# design.net
KiCad netlist of a schematic drawn in EasyEDA Pro
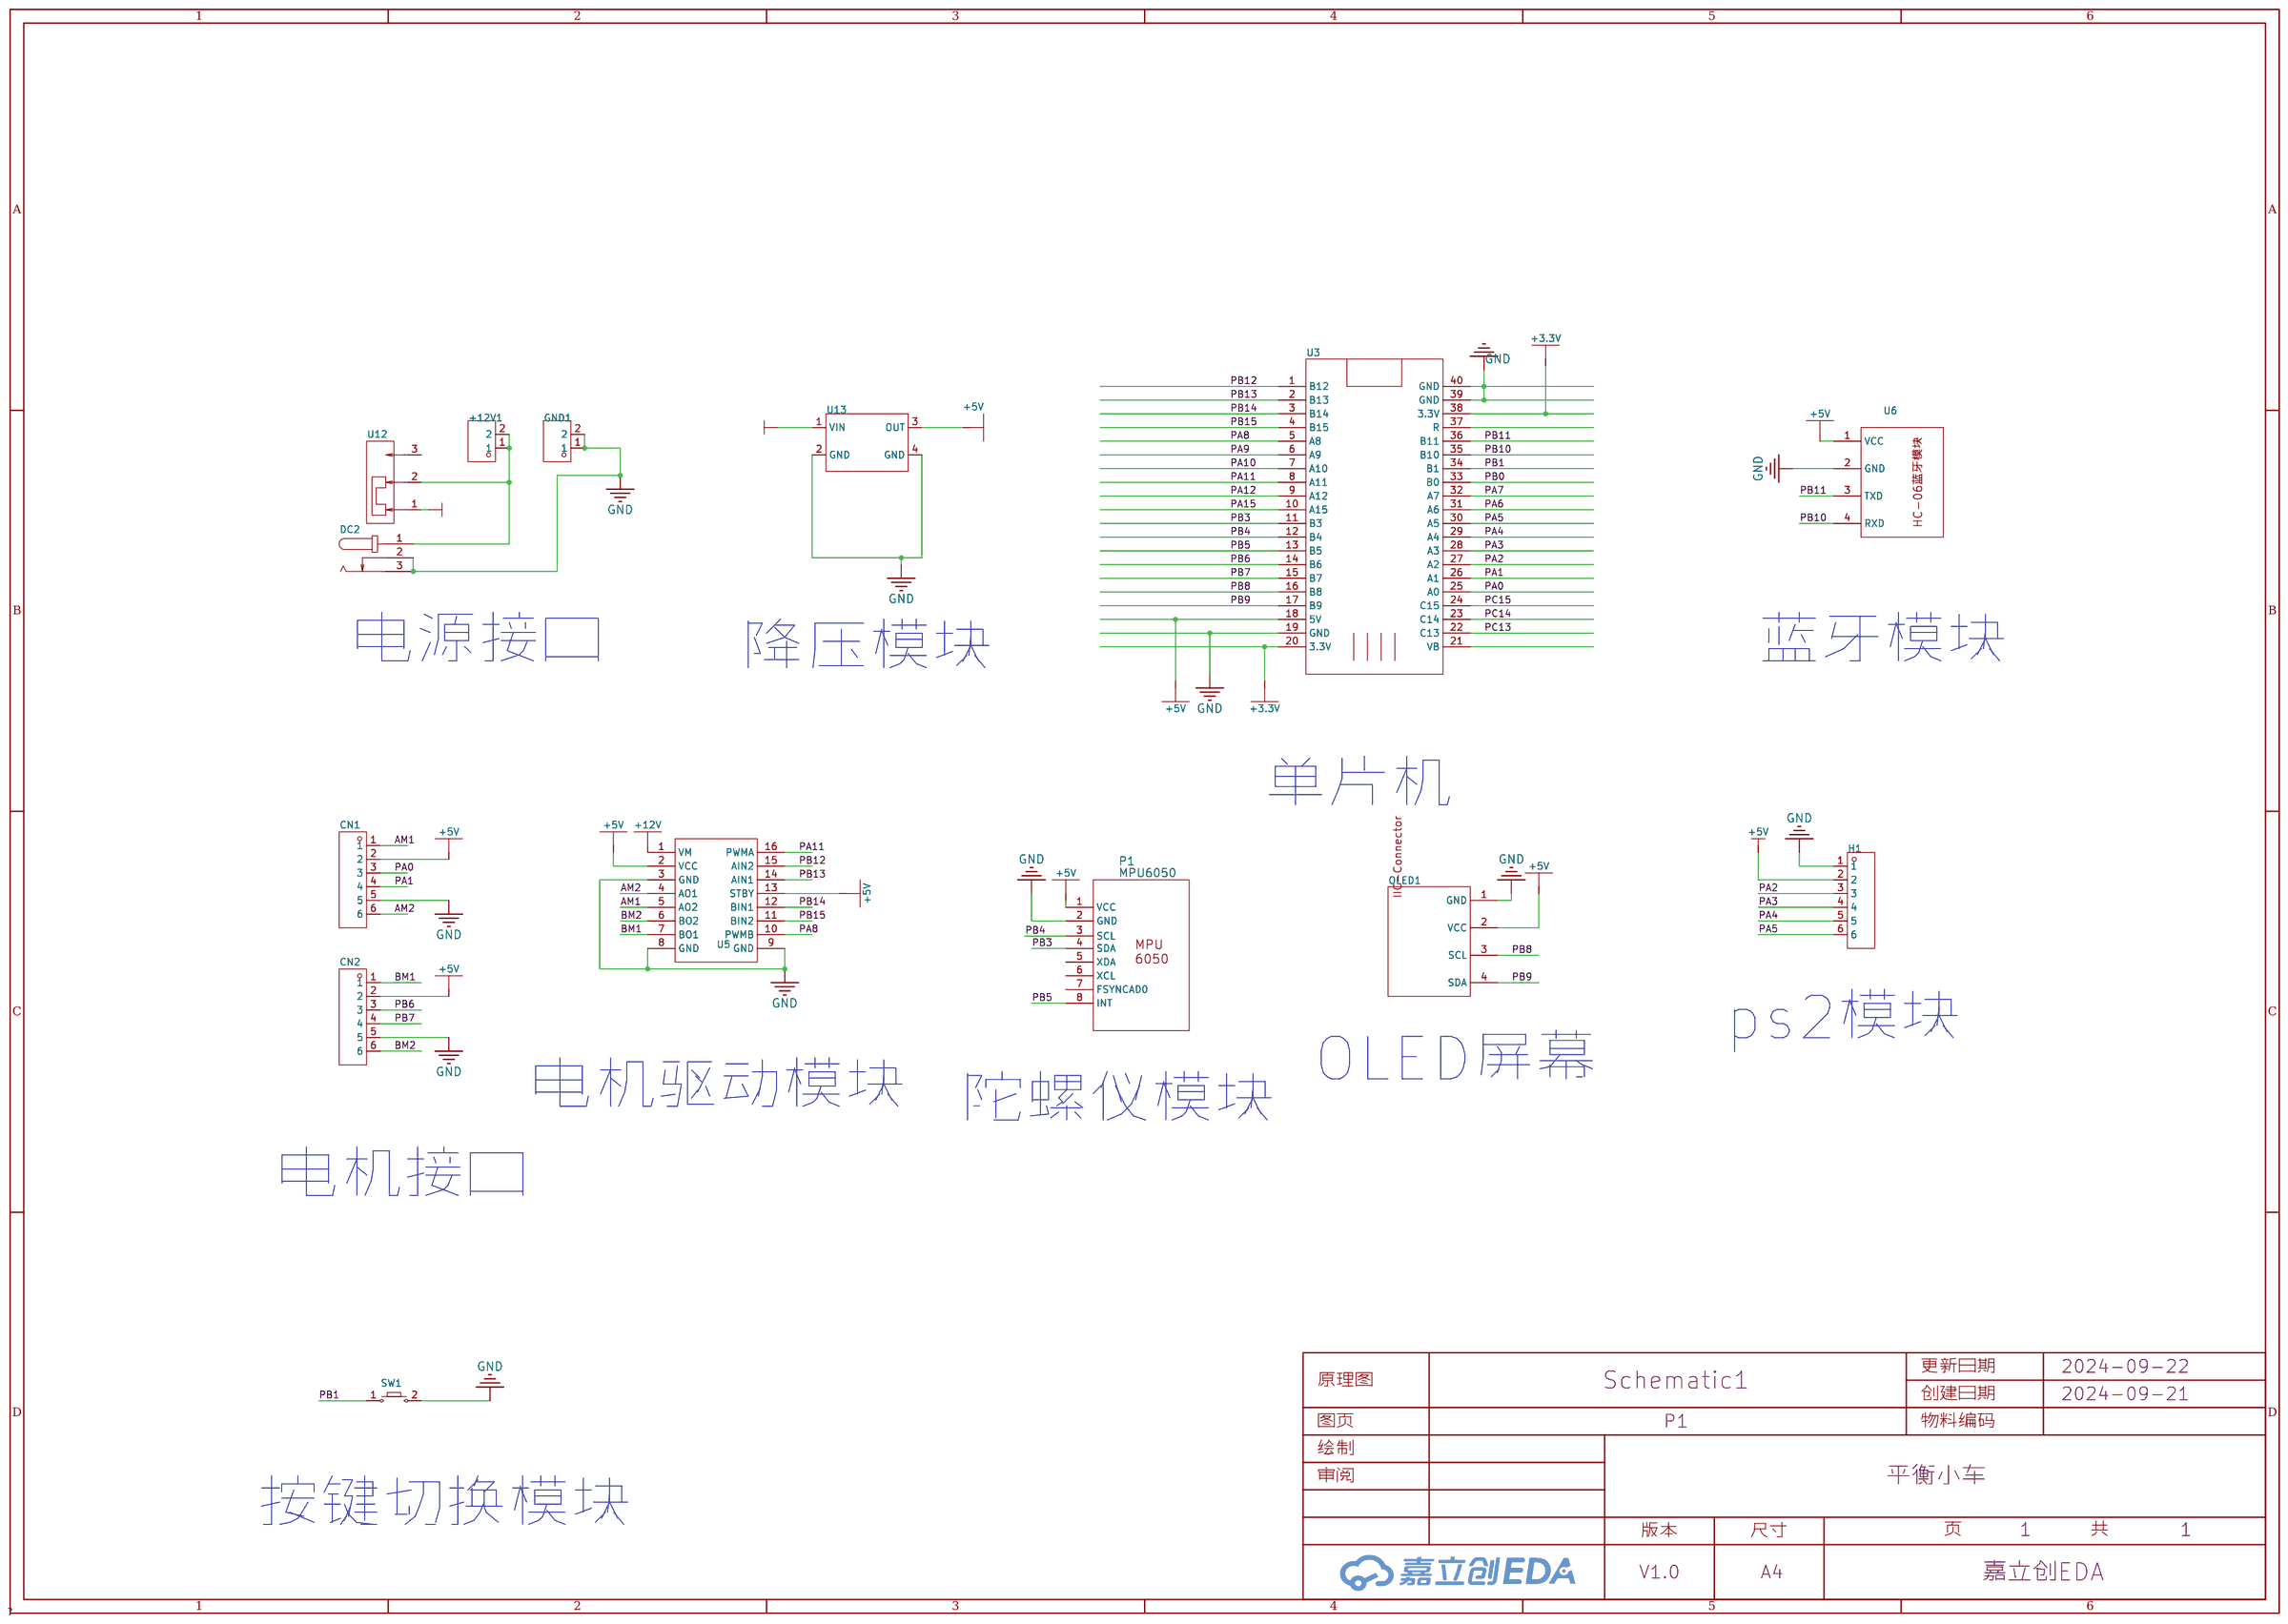
[diagram p0: schematic sheet]

(export (version "E")
  (design (tool "Eeschema 10.0.6"))
  (components
    (comp (ref "+12V1")
      (value "~")
      (description "2.54 1*2P 直排针 0.8u镀金 PBT RoHS,针长3*6mm")
      (fields
        (field (name "Manufacturer Part") "Z-211-0211-0021-001")
        (field (name "Manufacturer") "Nextron(台湾正凌)")
      )
      (libsource (lib "easyedapro") (part "Z-211-0211-0021-001"))
    )
    (comp (ref "CN1")
      (value "PH2.0-6P")
      (fields (field (name "Manufacturer Part") "PH2.0-4P") (field (name "Manufacturer") "CAX(创都)"))
      (libsource (lib "easyedapro") (part "PH2.0-6P"))
    )
    (comp (ref "CN2")
      (value "PH2.0-6P")
      (fields (field (name "Manufacturer Part") "PH2.0-4P") (field (name "Manufacturer") "CAX(创都)"))
      (libsource (lib "easyedapro") (part "ph2.0-6p"))
    )
    (comp (ref "DC2")
      (value "~")
      (description "连接器类型:DC电源插座;安装方式:弯插;触点内径:-;触点外径:6.4mm;额定电流:1A;额定电压:30V;工作温度范围:-25~+70;")
      (fields
        (field (name "Manufacturer Part") "KH-DC-005-2.5")
        (field (name "Manufacturer") "kinghelm(金航标)")
      )
      (libsource (lib "easyedapro") (part "KH-DC-005-2.5"))
    )
    (comp (ref "GND1")
      (value "~")
      (description "2.54 1*2P 直排针 0.8u镀金 PBT RoHS,针长3*6mm")
      (fields
        (field (name "Manufacturer Part") "Z-211-0211-0021-001")
        (field (name "Manufacturer") "Nextron(台湾正凌)")
      )
      (libsource (lib "easyedapro") (part "Z-211-0211-0021-001"))
    )
    (comp (ref "H1")
      (value "PZ254V-11-06P")
      (footprint "easyedapro:HDR-TH_6P-P2.54-V-M")
      (fields (field (name "Manufacturer") "XFCN(兴飞)"))
      (libsource (lib "easyedapro") (part "PZ254V-11-06P"))
    )
    (comp (ref "OLED1")
      (value "~")
      (fields (field (name "Manufacturer Part") "0.96OLED_4P_MODULE_JX"))
      (libsource (lib "easyedapro") (part "0.96OLED_4P_MODULE_JX"))
    )
    (comp (ref "P1") (value "MPU6050") (libsource (lib "easyedapro") (part "MPU6050")))
    (comp (ref "SW1")
      (value "~")
      (footprint "easyedapro:Key_SMD_3x4x2")
      (libsource (lib "easyedapro") (part "轻触按键x2"))
    )
    (comp (ref "U3") (value "~") (libsource (lib "easyedapro") (part "STM32F103C8T6核心板")))
    (comp (ref "U5") (value "~") (libsource (lib "easyedapro") (part "TB6612FNG模块")))
    (comp (ref "U6") (value "蓝牙模块HC-06") (libsource (lib "easyedapro") (part "蓝牙模块HC-06")))
    (comp (ref "U12")
      (value "SS-12D10-G5")
      (footprint "easyedapro:SW-TH_SS-12D10-G050")
      (description "电路结构:单刀双掷;安装方式:直插;开关颜色:黑色;滑钮形状:矩形柱状;引脚样式:PC引脚;开关长度:12.7mm;开关宽度:6.7mm;开关高度:11.3mm;")
      (fields (field (name "Manufacturer") "DEALON(德艺隆)"))
      (libsource (lib "easyedapro") (part "SS-12D10-G5"))
    )
    (comp (ref "U13")
      (value "~")
      (footprint "easyedapro:MP1584模块")
      (libsource (lib "easyedapro") (part "MP1584模块"))
    )
  )
  (nets
    (net (code "1") (name "+3.3V") (class "Default")
      (node (ref "U3") (pin "20") (pinfunction "3.3V_20") (pintype "unspecified"))
      (node (ref "U3") (pin "38") (pinfunction "3.3V_38") (pintype "unspecified"))
    )
    (net (code "2") (name "+5V") (class "Default")
      (node (ref "CN1") (pin "2") (pinfunction "2_2") (pintype "input"))
      (node (ref "CN2") (pin "2") (pinfunction "2_2") (pintype "input"))
      (node (ref "H1") (pin "2") (pinfunction "2_2") (pintype "unspecified"))
      (node (ref "OLED1") (pin "2") (pinfunction "VCC_2") (pintype "input"))
      (node (ref "P1") (pin "1") (pinfunction "VCC_1") (pintype "input"))
      (node (ref "U13") (pin "3") (pinfunction "OUT_3") (pintype "unspecified"))
      (node (ref "U3") (pin "18") (pinfunction "5V_18") (pintype "unspecified"))
      (node (ref "U5") (pin "13") (pinfunction "STBY_13") (pintype "input"))
      (node (ref "U5") (pin "2") (pinfunction "VCC_2") (pintype "input"))
      (node (ref "U6") (pin "1") (pinfunction "VCC_1") (pintype "unspecified"))
    )
    (net (code "3") (name "+12V") (class "Default")
      (node (ref "U12") (pin "1") (pinfunction "1_1") (pintype "input"))
      (node (ref "U13") (pin "1") (pinfunction "VIN_1") (pintype "unspecified"))
      (node (ref "U5") (pin "1") (pinfunction "VM_1") (pintype "input"))
    )
    (net (code "4") (name "/AM1") (class "Default")
      (node (ref "CN1") (pin "1") (pinfunction "1_1") (pintype "input"))
      (node (ref "U5") (pin "5") (pinfunction "AO2_5") (pintype "input"))
    )
    (net (code "5") (name "/AM2") (class "Default")
      (node (ref "CN1") (pin "6") (pinfunction "6_6") (pintype "input"))
      (node (ref "U5") (pin "4") (pinfunction "AO1_4") (pintype "input"))
    )
    (net (code "6") (name "/BM1") (class "Default")
      (node (ref "CN2") (pin "1") (pinfunction "1_1") (pintype "input"))
      (node (ref "U5") (pin "7") (pinfunction "BO1_7") (pintype "input"))
    )
    (net (code "7") (name "/BM2") (class "Default")
      (node (ref "CN2") (pin "6") (pinfunction "6_6") (pintype "input"))
      (node (ref "U5") (pin "6") (pinfunction "BO2_6") (pintype "input"))
    )
    (net (code "8") (name "/PA0") (class "Default")
      (node (ref "CN1") (pin "3") (pinfunction "3_3") (pintype "input"))
      (node (ref "U3") (pin "25") (pinfunction "A0_25") (pintype "unspecified"))
    )
    (net (code "9") (name "/PA1") (class "Default")
      (node (ref "CN1") (pin "4") (pinfunction "4_4") (pintype "input"))
      (node (ref "U3") (pin "26") (pinfunction "A1_26") (pintype "unspecified"))
    )
    (net (code "10") (name "/PA2") (class "Default")
      (node (ref "H1") (pin "3") (pinfunction "3_3") (pintype "unspecified"))
      (node (ref "U3") (pin "27") (pinfunction "A2_27") (pintype "unspecified"))
    )
    (net (code "11") (name "/PA3") (class "Default")
      (node (ref "H1") (pin "4") (pinfunction "4_4") (pintype "unspecified"))
      (node (ref "U3") (pin "28") (pinfunction "A3_28") (pintype "unspecified"))
    )
    (net (code "12") (name "/PA4") (class "Default")
      (node (ref "H1") (pin "5") (pinfunction "5_5") (pintype "unspecified"))
      (node (ref "U3") (pin "29") (pinfunction "A4_29") (pintype "unspecified"))
    )
    (net (code "13") (name "/PA5") (class "Default")
      (node (ref "H1") (pin "6") (pinfunction "6_6") (pintype "unspecified"))
      (node (ref "U3") (pin "30") (pinfunction "A5_30") (pintype "unspecified"))
    )
    (net (code "14") (name "/PA6") (class "Default")
      (node (ref "U3") (pin "31") (pinfunction "A6_31") (pintype "unspecified"))
    )
    (net (code "15") (name "/PA7") (class "Default")
      (node (ref "U3") (pin "32") (pinfunction "A7_32") (pintype "unspecified"))
    )
    (net (code "16") (name "/PA8") (class "Default")
      (node (ref "U3") (pin "5") (pinfunction "A8_5") (pintype "unspecified"))
      (node (ref "U5") (pin "10") (pinfunction "PWMB_10") (pintype "input"))
    )
    (net (code "17") (name "/PA9") (class "Default")
      (node (ref "U3") (pin "6") (pinfunction "A9_6") (pintype "unspecified"))
    )
    (net (code "18") (name "/PA10") (class "Default")
      (node (ref "U3") (pin "7") (pinfunction "A10_7") (pintype "unspecified"))
    )
    (net (code "19") (name "/PA11") (class "Default")
      (node (ref "U3") (pin "8") (pinfunction "A11_8") (pintype "unspecified"))
      (node (ref "U5") (pin "16") (pinfunction "PWMA_16") (pintype "input"))
    )
    (net (code "20") (name "/PA12") (class "Default")
      (node (ref "U3") (pin "9") (pinfunction "A12_9") (pintype "unspecified"))
    )
    (net (code "21") (name "/PA15") (class "Default")
      (node (ref "U3") (pin "10") (pinfunction "A15_10") (pintype "unspecified"))
    )
    (net (code "22") (name "/PB0") (class "Default")
      (node (ref "U3") (pin "33") (pinfunction "B0_33") (pintype "unspecified"))
    )
    (net (code "23") (name "/PB1") (class "Default")
      (node (ref "SW1") (pin "1") (pinfunction "1_1") (pintype "input"))
      (node (ref "U3") (pin "34") (pinfunction "B1_34") (pintype "unspecified"))
    )
    (net (code "24") (name "/PB3") (class "Default")
      (node (ref "P1") (pin "4") (pinfunction "SDA_4") (pintype "input"))
      (node (ref "U3") (pin "11") (pinfunction "B3_11") (pintype "unspecified"))
    )
    (net (code "25") (name "/PB4") (class "Default")
      (node (ref "P1") (pin "3") (pinfunction "SCL_3") (pintype "input"))
      (node (ref "U3") (pin "12") (pinfunction "B4_12") (pintype "unspecified"))
    )
    (net (code "26") (name "/PB5") (class "Default")
      (node (ref "P1") (pin "8") (pinfunction "INT_8") (pintype "input"))
      (node (ref "U3") (pin "13") (pinfunction "B5_13") (pintype "unspecified"))
    )
    (net (code "27") (name "/PB6") (class "Default")
      (node (ref "CN2") (pin "3") (pinfunction "3_3") (pintype "input"))
      (node (ref "U3") (pin "14") (pinfunction "B6_14") (pintype "unspecified"))
    )
    (net (code "28") (name "/PB7") (class "Default")
      (node (ref "CN2") (pin "4") (pinfunction "4_4") (pintype "input"))
      (node (ref "U3") (pin "15") (pinfunction "B7_15") (pintype "unspecified"))
    )
    (net (code "29") (name "/PB8") (class "Default")
      (node (ref "OLED1") (pin "3") (pinfunction "SCL_3") (pintype "input"))
      (node (ref "U3") (pin "16") (pinfunction "B8_16") (pintype "unspecified"))
    )
    (net (code "30") (name "/PB9") (class "Default")
      (node (ref "OLED1") (pin "4") (pinfunction "SDA_4") (pintype "input"))
      (node (ref "U3") (pin "17") (pinfunction "B9_17") (pintype "unspecified"))
    )
    (net (code "31") (name "/PB10") (class "Default")
      (node (ref "U3") (pin "35") (pinfunction "B10_35") (pintype "unspecified"))
      (node (ref "U6") (pin "4") (pinfunction "RXD_4") (pintype "unspecified"))
    )
    (net (code "32") (name "/PB11") (class "Default")
      (node (ref "U3") (pin "36") (pinfunction "B11_36") (pintype "unspecified"))
      (node (ref "U6") (pin "3") (pinfunction "TXD_3") (pintype "unspecified"))
    )
    (net (code "33") (name "/PB12") (class "Default")
      (node (ref "U3") (pin "1") (pinfunction "B12_1") (pintype "unspecified"))
      (node (ref "U5") (pin "15") (pinfunction "AIN2_15") (pintype "input"))
    )
    (net (code "34") (name "/PB13") (class "Default")
      (node (ref "U3") (pin "2") (pinfunction "B13_2") (pintype "unspecified"))
      (node (ref "U5") (pin "14") (pinfunction "AIN1_14") (pintype "input"))
    )
    (net (code "35") (name "/PB14") (class "Default")
      (node (ref "U3") (pin "3") (pinfunction "B14_3") (pintype "unspecified"))
      (node (ref "U5") (pin "12") (pinfunction "BIN1_12") (pintype "input"))
    )
    (net (code "36") (name "/PB15") (class "Default")
      (node (ref "U3") (pin "4") (pinfunction "B15_4") (pintype "unspecified"))
      (node (ref "U5") (pin "11") (pinfunction "BIN2_11") (pintype "input"))
    )
    (net (code "37") (name "/PC13") (class "Default")
      (node (ref "U3") (pin "22") (pinfunction "C13_22") (pintype "unspecified"))
    )
    (net (code "38") (name "/PC14") (class "Default")
      (node (ref "U3") (pin "23") (pinfunction "C14_23") (pintype "unspecified"))
    )
    (net (code "39") (name "/PC15") (class "Default")
      (node (ref "U3") (pin "24") (pinfunction "C15_24") (pintype "unspecified"))
    )
    (net (code "40") (name "GND") (class "Default")
      (node (ref "CN1") (pin "5") (pinfunction "5_5") (pintype "input"))
      (node (ref "CN2") (pin "5") (pinfunction "5_5") (pintype "input"))
      (node (ref "DC2") (pin "2") (pinfunction "2_2") (pintype "input"))
      (node (ref "DC2") (pin "3") (pinfunction "3_3") (pintype "input"))
      (node (ref "GND1") (pin "1") (pinfunction "1_1") (pintype "input"))
      (node (ref "GND1") (pin "2") (pinfunction "2_2") (pintype "input"))
      (node (ref "H1") (pin "1") (pinfunction "1_1") (pintype "unspecified"))
      (node (ref "OLED1") (pin "1") (pinfunction "GND_1") (pintype "input"))
      (node (ref "P1") (pin "2") (pinfunction "GND_2") (pintype "input"))
      (node (ref "SW1") (pin "2") (pinfunction "2_2") (pintype "input"))
      (node (ref "U13") (pin "2") (pinfunction "GND_2") (pintype "unspecified"))
      (node (ref "U13") (pin "4") (pinfunction "GND_4") (pintype "unspecified"))
      (node (ref "U3") (pin "19") (pinfunction "GND_19") (pintype "unspecified"))
      (node (ref "U3") (pin "39") (pinfunction "GND_39") (pintype "unspecified"))
      (node (ref "U3") (pin "40") (pinfunction "GND_40") (pintype "unspecified"))
      (node (ref "U5") (pin "3") (pinfunction "GND_3") (pintype "input"))
      (node (ref "U5") (pin "8") (pinfunction "GND_8") (pintype "input"))
      (node (ref "U5") (pin "9") (pinfunction "GND_9") (pintype "input"))
      (node (ref "U6") (pin "2") (pinfunction "GND_2") (pintype "unspecified"))
    )
    (net (code "41") (name "Net-(+12V1-Pad1)") (class "Default")
      (node (ref "+12V1") (pin "1") (pinfunction "1_1") (pintype "input"))
      (node (ref "+12V1") (pin "2") (pinfunction "2_2") (pintype "input"))
      (node (ref "DC2") (pin "1") (pinfunction "1_1") (pintype "input"))
      (node (ref "U12") (pin "2") (pinfunction "2_2") (pintype "input"))
    )
    (net (code "42") (name "unconnected-(P1-FSYNCAD0-Pad7)") (class "Default")
      (node (ref "P1") (pin "7") (pinfunction "FSYNCAD0_7") (pintype "input"))
    )
    (net (code "43") (name "unconnected-(P1-XCL-Pad6)") (class "Default")
      (node (ref "P1") (pin "6") (pinfunction "XCL_6") (pintype "input"))
    )
    (net (code "44") (name "unconnected-(P1-XDA-Pad5)") (class "Default")
      (node (ref "P1") (pin "5") (pinfunction "XDA_5") (pintype "input"))
    )
    (net (code "45") (name "unconnected-(U3-R-Pad37)") (class "Default")
      (node (ref "U3") (pin "37") (pinfunction "R_37") (pintype "unspecified"))
    )
    (net (code "46") (name "unconnected-(U3-VB-Pad21)") (class "Default")
      (node (ref "U3") (pin "21") (pinfunction "VB_21") (pintype "unspecified"))
    )
    (net (code "47") (name "unconnected-(U12-Pad3)") (class "Default")
      (node (ref "U12") (pin "3") (pinfunction "3_3") (pintype "input"))
    )
  )
)
